# Nav_Ducer_ADC.net
KiCad netlist of a schematic drawn in Altium Designer
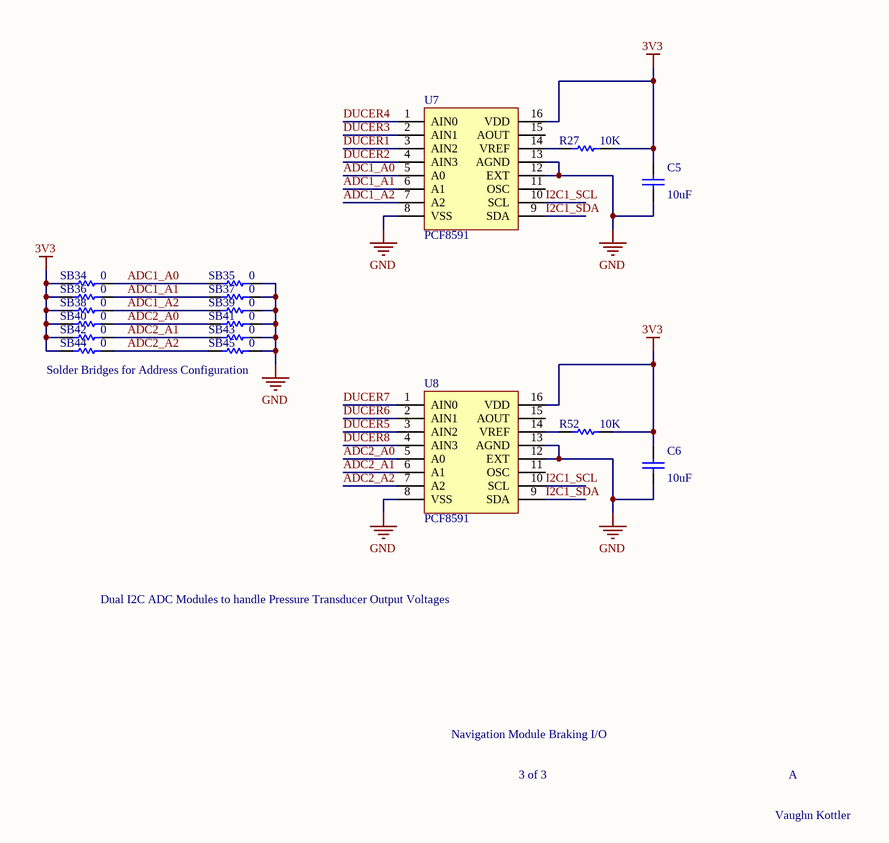
[diagram p0: Nav_Ducer_ADC.SchDoc]

(export (version "E")
  (design (tool "Eeschema 10.0.6"))
  (components
    (comp (ref "C5")
      (value "10uF")
      (footprint "C1206")
      (description "Capacitor")
      (fields (field (name "Comment") "Cap") (field (name "PUBLISHER") "Altium Limited"))
      (libsource (lib "Miscellaneous Devices") (part "Cap"))
    )
    (comp (ref "C6")
      (value "10uF")
      (footprint "C1206")
      (description "Capacitor")
      (fields (field (name "Comment") "Cap") (field (name "PUBLISHER") "Altium Limited"))
      (libsource (lib "Miscellaneous Devices") (part "Cap"))
    )
    (comp (ref "R27")
      (value "10K")
      (footprint "6-0805_M")
      (description "Resistor")
      (fields (field (name "Comment") "Res1") (field (name "PUBLISHER") "Altium Limited"))
      (libsource (lib "Miscellaneous Devices") (part "Res1"))
    )
    (comp (ref "R52")
      (value "10K")
      (footprint "6-0805_M")
      (description "Resistor")
      (fields (field (name "Comment") "Res1") (field (name "PUBLISHER") "Altium Limited"))
      (libsource (lib "Miscellaneous Devices") (part "Res1"))
    )
    (comp (ref "SB34")
      (value "0")
      (footprint "6-0805_M")
      (description "Resistor")
      (fields (field (name "Comment") "Res1") (field (name "PUBLISHER") "Altium Limited"))
      (libsource (lib "Miscellaneous Devices") (part "Res1"))
    )
    (comp (ref "SB35")
      (value "0")
      (footprint "6-0805_M")
      (description "Resistor")
      (fields (field (name "Comment") "Res1") (field (name "PUBLISHER") "Altium Limited"))
      (libsource (lib "Miscellaneous Devices") (part "Res1"))
    )
    (comp (ref "SB36")
      (value "0")
      (footprint "6-0805_M")
      (description "Resistor")
      (fields (field (name "Comment") "Res1") (field (name "PUBLISHER") "Altium Limited"))
      (libsource (lib "Miscellaneous Devices") (part "Res1"))
    )
    (comp (ref "SB37")
      (value "0")
      (footprint "6-0805_M")
      (description "Resistor")
      (fields (field (name "Comment") "Res1") (field (name "PUBLISHER") "Altium Limited"))
      (libsource (lib "Miscellaneous Devices") (part "Res1"))
    )
    (comp (ref "SB38")
      (value "0")
      (footprint "6-0805_M")
      (description "Resistor")
      (fields (field (name "Comment") "Res1") (field (name "PUBLISHER") "Altium Limited"))
      (libsource (lib "Miscellaneous Devices") (part "Res1"))
    )
    (comp (ref "SB39")
      (value "0")
      (footprint "6-0805_M")
      (description "Resistor")
      (fields (field (name "Comment") "Res1") (field (name "PUBLISHER") "Altium Limited"))
      (libsource (lib "Miscellaneous Devices") (part "Res1"))
    )
    (comp (ref "SB40")
      (value "0")
      (footprint "6-0805_M")
      (description "Resistor")
      (fields (field (name "Comment") "Res1") (field (name "PUBLISHER") "Altium Limited"))
      (libsource (lib "Miscellaneous Devices") (part "Res1"))
    )
    (comp (ref "SB41")
      (value "0")
      (footprint "6-0805_M")
      (description "Resistor")
      (fields (field (name "Comment") "Res1") (field (name "PUBLISHER") "Altium Limited"))
      (libsource (lib "Miscellaneous Devices") (part "Res1"))
    )
    (comp (ref "SB42")
      (value "0")
      (footprint "6-0805_M")
      (description "Resistor")
      (fields (field (name "Comment") "Res1") (field (name "PUBLISHER") "Altium Limited"))
      (libsource (lib "Miscellaneous Devices") (part "Res1"))
    )
    (comp (ref "SB43")
      (value "0")
      (footprint "6-0805_M")
      (description "Resistor")
      (fields (field (name "Comment") "Res1") (field (name "PUBLISHER") "Altium Limited"))
      (libsource (lib "Miscellaneous Devices") (part "Res1"))
    )
    (comp (ref "SB44")
      (value "0")
      (footprint "6-0805_M")
      (description "Resistor")
      (fields (field (name "Comment") "Res1") (field (name "PUBLISHER") "Altium Limited"))
      (libsource (lib "Miscellaneous Devices") (part "Res1"))
    )
    (comp (ref "SB45")
      (value "0")
      (footprint "6-0805_M")
      (description "Resistor")
      (fields (field (name "Comment") "Res1") (field (name "PUBLISHER") "Altium Limited"))
      (libsource (lib "Miscellaneous Devices") (part "Res1"))
    )
    (comp (ref "U7")
      (value "PCF8591")
      (footprint "16-SOIC")
      (description "8-bit A/D and D/A")
      (libsource (lib "ic") (part "PCF8591"))
    )
    (comp (ref "U8")
      (value "PCF8591")
      (footprint "16-SOIC")
      (description "8-bit A/D and D/A")
      (libsource (lib "ic") (part "PCF8591"))
    )
  )
  (nets
    (net (code "1") (name "/ADC1_A0") (class "Default")
      (node (ref "SB34") (pin "1") (pinfunction "1_1") (pintype "passive"))
      (node (ref "SB35") (pin "2") (pinfunction "2_2") (pintype "passive"))
      (node (ref "U7") (pin "5") (pinfunction "A0_5") (pintype "passive"))
    )
    (net (code "2") (name "/ADC1_A1") (class "Default")
      (node (ref "SB36") (pin "1") (pinfunction "1_1") (pintype "passive"))
      (node (ref "SB37") (pin "2") (pinfunction "2_2") (pintype "passive"))
      (node (ref "U7") (pin "6") (pinfunction "A1_6") (pintype "passive"))
    )
    (net (code "3") (name "/ADC1_A2") (class "Default")
      (node (ref "SB38") (pin "1") (pinfunction "1_1") (pintype "passive"))
      (node (ref "SB39") (pin "2") (pinfunction "2_2") (pintype "passive"))
      (node (ref "U7") (pin "7") (pinfunction "A2_7") (pintype "passive"))
    )
    (net (code "4") (name "/ADC2_A0") (class "Default")
      (node (ref "SB40") (pin "1") (pinfunction "1_1") (pintype "passive"))
      (node (ref "SB41") (pin "2") (pinfunction "2_2") (pintype "passive"))
      (node (ref "U8") (pin "5") (pinfunction "A0_5") (pintype "passive"))
    )
    (net (code "5") (name "/ADC2_A1") (class "Default")
      (node (ref "SB42") (pin "1") (pinfunction "1_1") (pintype "passive"))
      (node (ref "SB43") (pin "2") (pinfunction "2_2") (pintype "passive"))
      (node (ref "U8") (pin "6") (pinfunction "A1_6") (pintype "passive"))
    )
    (net (code "6") (name "/ADC2_A2") (class "Default")
      (node (ref "SB44") (pin "1") (pinfunction "1_1") (pintype "passive"))
      (node (ref "SB45") (pin "2") (pinfunction "2_2") (pintype "passive"))
      (node (ref "U8") (pin "7") (pinfunction "A2_7") (pintype "passive"))
    )
    (net (code "7") (name "/DUCER1") (class "Default")
      (node (ref "U7") (pin "3") (pinfunction "AIN2_3") (pintype "passive"))
    )
    (net (code "8") (name "/DUCER2") (class "Default")
      (node (ref "U7") (pin "4") (pinfunction "AIN3_4") (pintype "passive"))
    )
    (net (code "9") (name "/DUCER3") (class "Default")
      (node (ref "U7") (pin "2") (pinfunction "AIN1_2") (pintype "passive"))
    )
    (net (code "10") (name "/DUCER4") (class "Default")
      (node (ref "U7") (pin "1") (pinfunction "AIN0_1") (pintype "passive"))
    )
    (net (code "11") (name "/DUCER5") (class "Default")
      (node (ref "U8") (pin "3") (pinfunction "AIN2_3") (pintype "passive"))
    )
    (net (code "12") (name "/DUCER6") (class "Default")
      (node (ref "U8") (pin "2") (pinfunction "AIN1_2") (pintype "passive"))
    )
    (net (code "13") (name "/DUCER7") (class "Default")
      (node (ref "U8") (pin "1") (pinfunction "AIN0_1") (pintype "passive"))
    )
    (net (code "14") (name "/DUCER8") (class "Default")
      (node (ref "U8") (pin "4") (pinfunction "AIN3_4") (pintype "passive"))
    )
    (net (code "15") (name "/I2C1_SCL") (class "Default")
      (node (ref "U7") (pin "10") (pinfunction "SCL_10") (pintype "passive"))
      (node (ref "U8") (pin "10") (pinfunction "SCL_10") (pintype "passive"))
    )
    (net (code "16") (name "/I2C1_SDA") (class "Default")
      (node (ref "U7") (pin "9") (pinfunction "SDA_9") (pintype "passive"))
      (node (ref "U8") (pin "9") (pinfunction "SDA_9") (pintype "passive"))
    )
    (net (code "17") (name "3V3") (class "Default")
      (node (ref "C5") (pin "2") (pinfunction "2_2") (pintype "passive"))
      (node (ref "C6") (pin "2") (pinfunction "2_2") (pintype "passive"))
      (node (ref "R27") (pin "1") (pinfunction "1_1") (pintype "passive"))
      (node (ref "R52") (pin "1") (pinfunction "1_1") (pintype "passive"))
      (node (ref "SB34") (pin "2") (pinfunction "2_2") (pintype "passive"))
      (node (ref "SB36") (pin "2") (pinfunction "2_2") (pintype "passive"))
      (node (ref "SB38") (pin "2") (pinfunction "2_2") (pintype "passive"))
      (node (ref "SB40") (pin "2") (pinfunction "2_2") (pintype "passive"))
      (node (ref "SB42") (pin "2") (pinfunction "2_2") (pintype "passive"))
      (node (ref "SB44") (pin "2") (pinfunction "2_2") (pintype "passive"))
      (node (ref "U7") (pin "16") (pinfunction "VDD_16") (pintype "passive"))
      (node (ref "U8") (pin "16") (pinfunction "VDD_16") (pintype "passive"))
    )
    (net (code "18") (name "GND") (class "Default")
      (node (ref "C5") (pin "1") (pinfunction "1_1") (pintype "passive"))
      (node (ref "C6") (pin "1") (pinfunction "1_1") (pintype "passive"))
      (node (ref "SB35") (pin "1") (pinfunction "1_1") (pintype "passive"))
      (node (ref "SB37") (pin "1") (pinfunction "1_1") (pintype "passive"))
      (node (ref "SB39") (pin "1") (pinfunction "1_1") (pintype "passive"))
      (node (ref "SB41") (pin "1") (pinfunction "1_1") (pintype "passive"))
      (node (ref "SB43") (pin "1") (pinfunction "1_1") (pintype "passive"))
      (node (ref "SB45") (pin "1") (pinfunction "1_1") (pintype "passive"))
      (node (ref "U7") (pin "12") (pinfunction "EXT_12") (pintype "passive"))
      (node (ref "U7") (pin "13") (pinfunction "AGND_13") (pintype "passive"))
      (node (ref "U7") (pin "8") (pinfunction "VSS_8") (pintype "passive"))
      (node (ref "U8") (pin "12") (pinfunction "EXT_12") (pintype "passive"))
      (node (ref "U8") (pin "13") (pinfunction "AGND_13") (pintype "passive"))
      (node (ref "U8") (pin "8") (pinfunction "VSS_8") (pintype "passive"))
    )
    (net (code "19") (name "Net-(U7-VREF)") (class "Default")
      (node (ref "R27") (pin "2") (pinfunction "2_2") (pintype "passive"))
      (node (ref "U7") (pin "14") (pinfunction "VREF_14") (pintype "passive"))
    )
    (net (code "20") (name "Net-(U8-VREF)") (class "Default")
      (node (ref "R52") (pin "2") (pinfunction "2_2") (pintype "passive"))
      (node (ref "U8") (pin "14") (pinfunction "VREF_14") (pintype "passive"))
    )
    (net (code "21") (name "unconnected-(U7-AOUT-Pad15)") (class "Default")
      (node (ref "U7") (pin "15") (pinfunction "AOUT_15") (pintype "passive"))
    )
    (net (code "22") (name "unconnected-(U7-OSC-Pad11)") (class "Default")
      (node (ref "U7") (pin "11") (pinfunction "OSC_11") (pintype "passive"))
    )
    (net (code "23") (name "unconnected-(U8-AOUT-Pad15)") (class "Default")
      (node (ref "U8") (pin "15") (pinfunction "AOUT_15") (pintype "passive"))
    )
    (net (code "24") (name "unconnected-(U8-OSC-Pad11)") (class "Default")
      (node (ref "U8") (pin "11") (pinfunction "OSC_11") (pintype "passive"))
    )
  )
)
